# battery_watcher.net
KiCad netlist of a schematic drawn in EAGLE
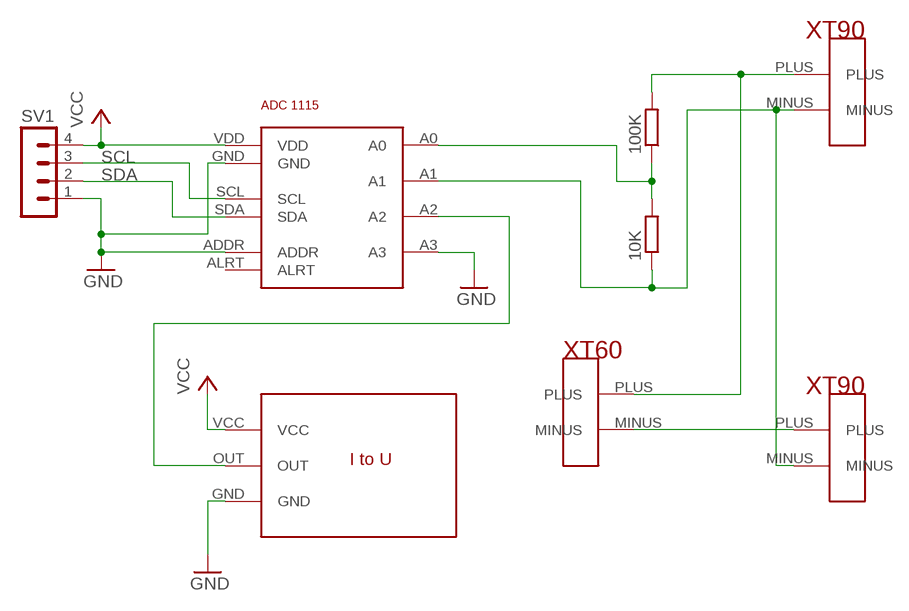
[diagram p0: schematic, sheet 1]

(export (version "E")
  (design (tool "Eeschema 10.0.6"))
  (components
    (comp (ref "10K")
      (value "R-EU_M1206")
      (footprint "eagle-import:M1206")
      (libsource (lib "eagle-import") (part "R-EU_M1206"))
    )
    (comp (ref "100K")
      (value "R-EU_M1206")
      (footprint "eagle-import:M1206")
      (libsource (lib "eagle-import") (part "R-EU_M1206"))
    )
    (comp (ref "SV1")
      (value "MA04-1")
      (footprint "eagle-import:MA04-1")
      (libsource (lib "eagle-import") (part "MA04-1"))
    )
    (comp (ref "U$1")
      (value "ADC1115")
      (footprint "eagle-import:ADC1115")
      (libsource (lib "eagle-import") (part "ADC1115"))
    )
    (comp (ref "U$2")
      (value "I2U_MODULE")
      (footprint "eagle-import:I2U")
      (libsource (lib "eagle-import") (part "I2U_MODULE"))
    )
    (comp (ref "U$3")
      (value "XT90")
      (footprint "eagle-import:XT90")
      (libsource (lib "eagle-import") (part "XT90"))
    )
    (comp (ref "U$4")
      (value "XT90")
      (footprint "eagle-import:XT90")
      (libsource (lib "eagle-import") (part "XT90"))
    )
    (comp (ref "U$5")
      (value "XT60")
      (footprint "eagle-import:XT60")
      (libsource (lib "eagle-import") (part "XT60"))
    )
  )
  (nets
    (net (code "1") (name "/SCL") (class "Default")
      (node (ref "SV1") (pin "3") (pinfunction "3_3") (pintype "passive"))
      (node (ref "U$1") (pin "SCL") (pinfunction "SCL_SCL") (pintype "bidirectional"))
    )
    (net (code "2") (name "/SDA") (class "Default")
      (node (ref "SV1") (pin "2") (pinfunction "2_2") (pintype "passive"))
      (node (ref "U$1") (pin "SDA") (pinfunction "SDA_SDA") (pintype "bidirectional"))
    )
    (net (code "3") (name "GND") (class "Default")
      (node (ref "SV1") (pin "1") (pinfunction "1_1") (pintype "passive"))
      (node (ref "U$1") (pin "A3") (pinfunction "A3_A3") (pintype "bidirectional"))
      (node (ref "U$1") (pin "ADDR") (pinfunction "ADDR_ADDR") (pintype "bidirectional"))
      (node (ref "U$1") (pin "GND") (pinfunction "GND_GND") (pintype "bidirectional"))
      (node (ref "U$2") (pin "GND") (pinfunction "GND_GND") (pintype "bidirectional"))
    )
    (net (code "4") (name "Net-(10K-Pad1)") (class "Default")
      (node (ref "10K") (pin "1") (pinfunction "1_1") (pintype "passive"))
      (node (ref "U$1") (pin "A1") (pinfunction "A1_A1") (pintype "bidirectional"))
      (node (ref "U$3") (pin "MINUS") (pinfunction "MINUS_MINUS") (pintype "bidirectional"))
      (node (ref "U$4") (pin "MINUS") (pinfunction "MINUS_MINUS") (pintype "bidirectional"))
    )
    (net (code "5") (name "Net-(100K-Pad1)") (class "Default")
      (node (ref "100K") (pin "1") (pinfunction "1_1") (pintype "passive"))
      (node (ref "10K") (pin "2") (pinfunction "2_2") (pintype "passive"))
      (node (ref "U$1") (pin "A0") (pinfunction "A0_A0") (pintype "bidirectional"))
    )
    (net (code "6") (name "Net-(100K-Pad2)") (class "Default")
      (node (ref "100K") (pin "2") (pinfunction "2_2") (pintype "passive"))
      (node (ref "U$4") (pin "PLUS") (pinfunction "PLUS_PLUS") (pintype "bidirectional"))
      (node (ref "U$5") (pin "PLUS") (pinfunction "PLUS_PLUS") (pintype "bidirectional"))
    )
    (net (code "7") (name "Net-(U$1-PadA2)") (class "Default")
      (node (ref "U$1") (pin "A2") (pinfunction "A2_A2") (pintype "bidirectional"))
      (node (ref "U$2") (pin "OUT") (pinfunction "OUT_OUT") (pintype "bidirectional"))
    )
    (net (code "8") (name "Net-(U$3-PadPLUS)") (class "Default")
      (node (ref "U$3") (pin "PLUS") (pinfunction "PLUS_PLUS") (pintype "bidirectional"))
      (node (ref "U$5") (pin "MINUS") (pinfunction "MINUS_MINUS") (pintype "bidirectional"))
    )
    (net (code "9") (name "VCC") (class "Default")
      (node (ref "SV1") (pin "4") (pinfunction "4_4") (pintype "passive"))
      (node (ref "U$1") (pin "VDD") (pinfunction "VDD_VDD") (pintype "bidirectional"))
      (node (ref "U$2") (pin "VCC") (pinfunction "VCC_VCC") (pintype "bidirectional"))
    )
    (net (code "10") (name "unconnected-(U$1-PadALRT)") (class "Default")
      (node (ref "U$1") (pin "ALRT") (pinfunction "ALRT_ALRT") (pintype "bidirectional"))
    )
  )
)
